# BandpassedGainAmpSMTMounthole.net
KiCad netlist of a schematic drawn in EAGLE
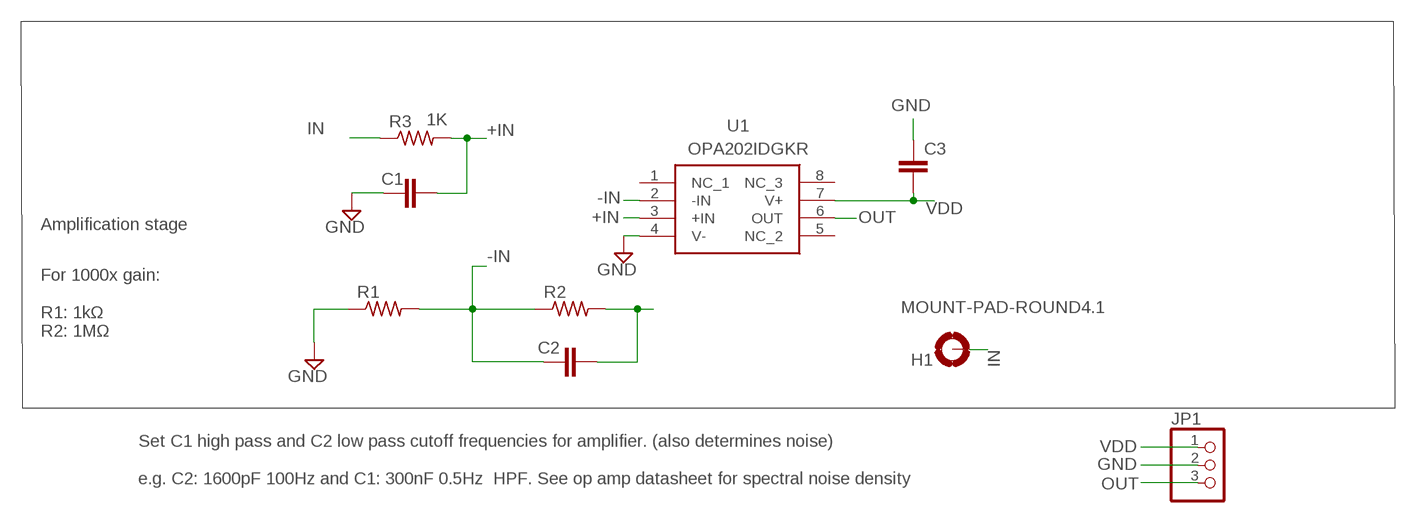
[diagram p0: schematic, sheet 1]

(export (version "E")
  (design (tool "Eeschema 10.0.6"))
  (components
    (comp (ref "C1")
      (value "C-EUC0402")
      (footprint "eagle-import:C0402")
      (libsource (lib "eagle-import") (part "C-EUC0402"))
    )
    (comp (ref "C2")
      (value "C-EUC0402")
      (footprint "eagle-import:C0402")
      (libsource (lib "eagle-import") (part "C-EUC0402"))
    )
    (comp (ref "C3")
      (value "C-EUC0402")
      (footprint "eagle-import:C0402")
      (libsource (lib "eagle-import") (part "C-EUC0402"))
    )
    (comp (ref "H1")
      (value "MOUNT-PAD-ROUND4.1")
      (footprint "eagle-import:4,1-PAD")
      (libsource (lib "eagle-import") (part "MOUNT-PAD-ROUND4.1"))
    )
    (comp (ref "JP1")
      (value "PINHD-1X3")
      (footprint "eagle-import:1X03")
      (libsource (lib "eagle-import") (part "PINHD-1X3"))
    )
    (comp (ref "R1")
      (value "R-US_R0402")
      (footprint "eagle-import:R0402")
      (libsource (lib "eagle-import") (part "R-US_R0402"))
    )
    (comp (ref "R2")
      (value "R-US_R0402")
      (footprint "eagle-import:R0402")
      (libsource (lib "eagle-import") (part "R-US_R0402"))
    )
    (comp (ref "R3")
      (value "1K")
      (footprint "eagle-import:R0402")
      (libsource (lib "eagle-import") (part "R-US_R0402"))
    )
    (comp (ref "U1")
      (value "OPA202IDGKR")
      (footprint "eagle-import:SOP65P490X110-8N")
      (fields (field (name "MOUSER_PART_NUMBER") "595-OPA202IDGKR"))
      (libsource (lib "eagle-import") (part "OPA202IDGKR"))
    )
  )
  (nets
    (net (code "1") (name "/+IN") (class "Default")
      (node (ref "C1") (pin "2") (pinfunction "2_2") (pintype "passive"))
      (node (ref "R3") (pin "2") (pinfunction "2_2") (pintype "passive"))
      (node (ref "U1") (pin "3") (pinfunction "+IN_3") (pintype "bidirectional"))
    )
    (net (code "2") (name "/-IN") (class "Default")
      (node (ref "C2") (pin "1") (pinfunction "1_1") (pintype "passive"))
      (node (ref "R1") (pin "2") (pinfunction "2_2") (pintype "passive"))
      (node (ref "R2") (pin "1") (pinfunction "1_1") (pintype "passive"))
      (node (ref "U1") (pin "2") (pinfunction "-IN_2") (pintype "bidirectional"))
    )
    (net (code "3") (name "/IN") (class "Default")
      (node (ref "H1") (pin "B4,1") (pinfunction "MOUNT_B4,1") (pintype "passive"))
      (node (ref "R3") (pin "1") (pinfunction "1_1") (pintype "passive"))
    )
    (net (code "4") (name "/OUT") (class "Default")
      (node (ref "JP1") (pin "3") (pinfunction "3_3") (pintype "passive"))
      (node (ref "U1") (pin "6") (pinfunction "OUT_6") (pintype "bidirectional"))
    )
    (net (code "5") (name "/VDD") (class "Default")
      (node (ref "C3") (pin "2") (pinfunction "2_2") (pintype "passive"))
      (node (ref "JP1") (pin "1") (pinfunction "1_1") (pintype "passive"))
      (node (ref "U1") (pin "7") (pinfunction "V+_7") (pintype "bidirectional"))
    )
    (net (code "6") (name "GND") (class "Default")
      (node (ref "C1") (pin "1") (pinfunction "1_1") (pintype "passive"))
      (node (ref "C3") (pin "1") (pinfunction "1_1") (pintype "passive"))
      (node (ref "JP1") (pin "2") (pinfunction "2_2") (pintype "passive"))
      (node (ref "R1") (pin "1") (pinfunction "1_1") (pintype "passive"))
      (node (ref "U1") (pin "4") (pinfunction "V-_4") (pintype "bidirectional"))
    )
    (net (code "7") (name "Net-(C2-Pad2)") (class "Default")
      (node (ref "C2") (pin "2") (pinfunction "2_2") (pintype "passive"))
      (node (ref "R2") (pin "2") (pinfunction "2_2") (pintype "passive"))
    )
    (net (code "8") (name "unconnected-(U1-NC_1-Pad1)") (class "Default")
      (node (ref "U1") (pin "1") (pinfunction "NC_1_1") (pintype "bidirectional"))
    )
    (net (code "9") (name "unconnected-(U1-NC_2-Pad5)") (class "Default")
      (node (ref "U1") (pin "5") (pinfunction "NC_2_5") (pintype "bidirectional"))
    )
    (net (code "10") (name "unconnected-(U1-NC_3-Pad8)") (class "Default")
      (node (ref "U1") (pin "8") (pinfunction "NC_3_8") (pintype "bidirectional"))
    )
  )
)
